# reflow_ofen.net
KiCad netlist of a schematic drawn in EAGLE
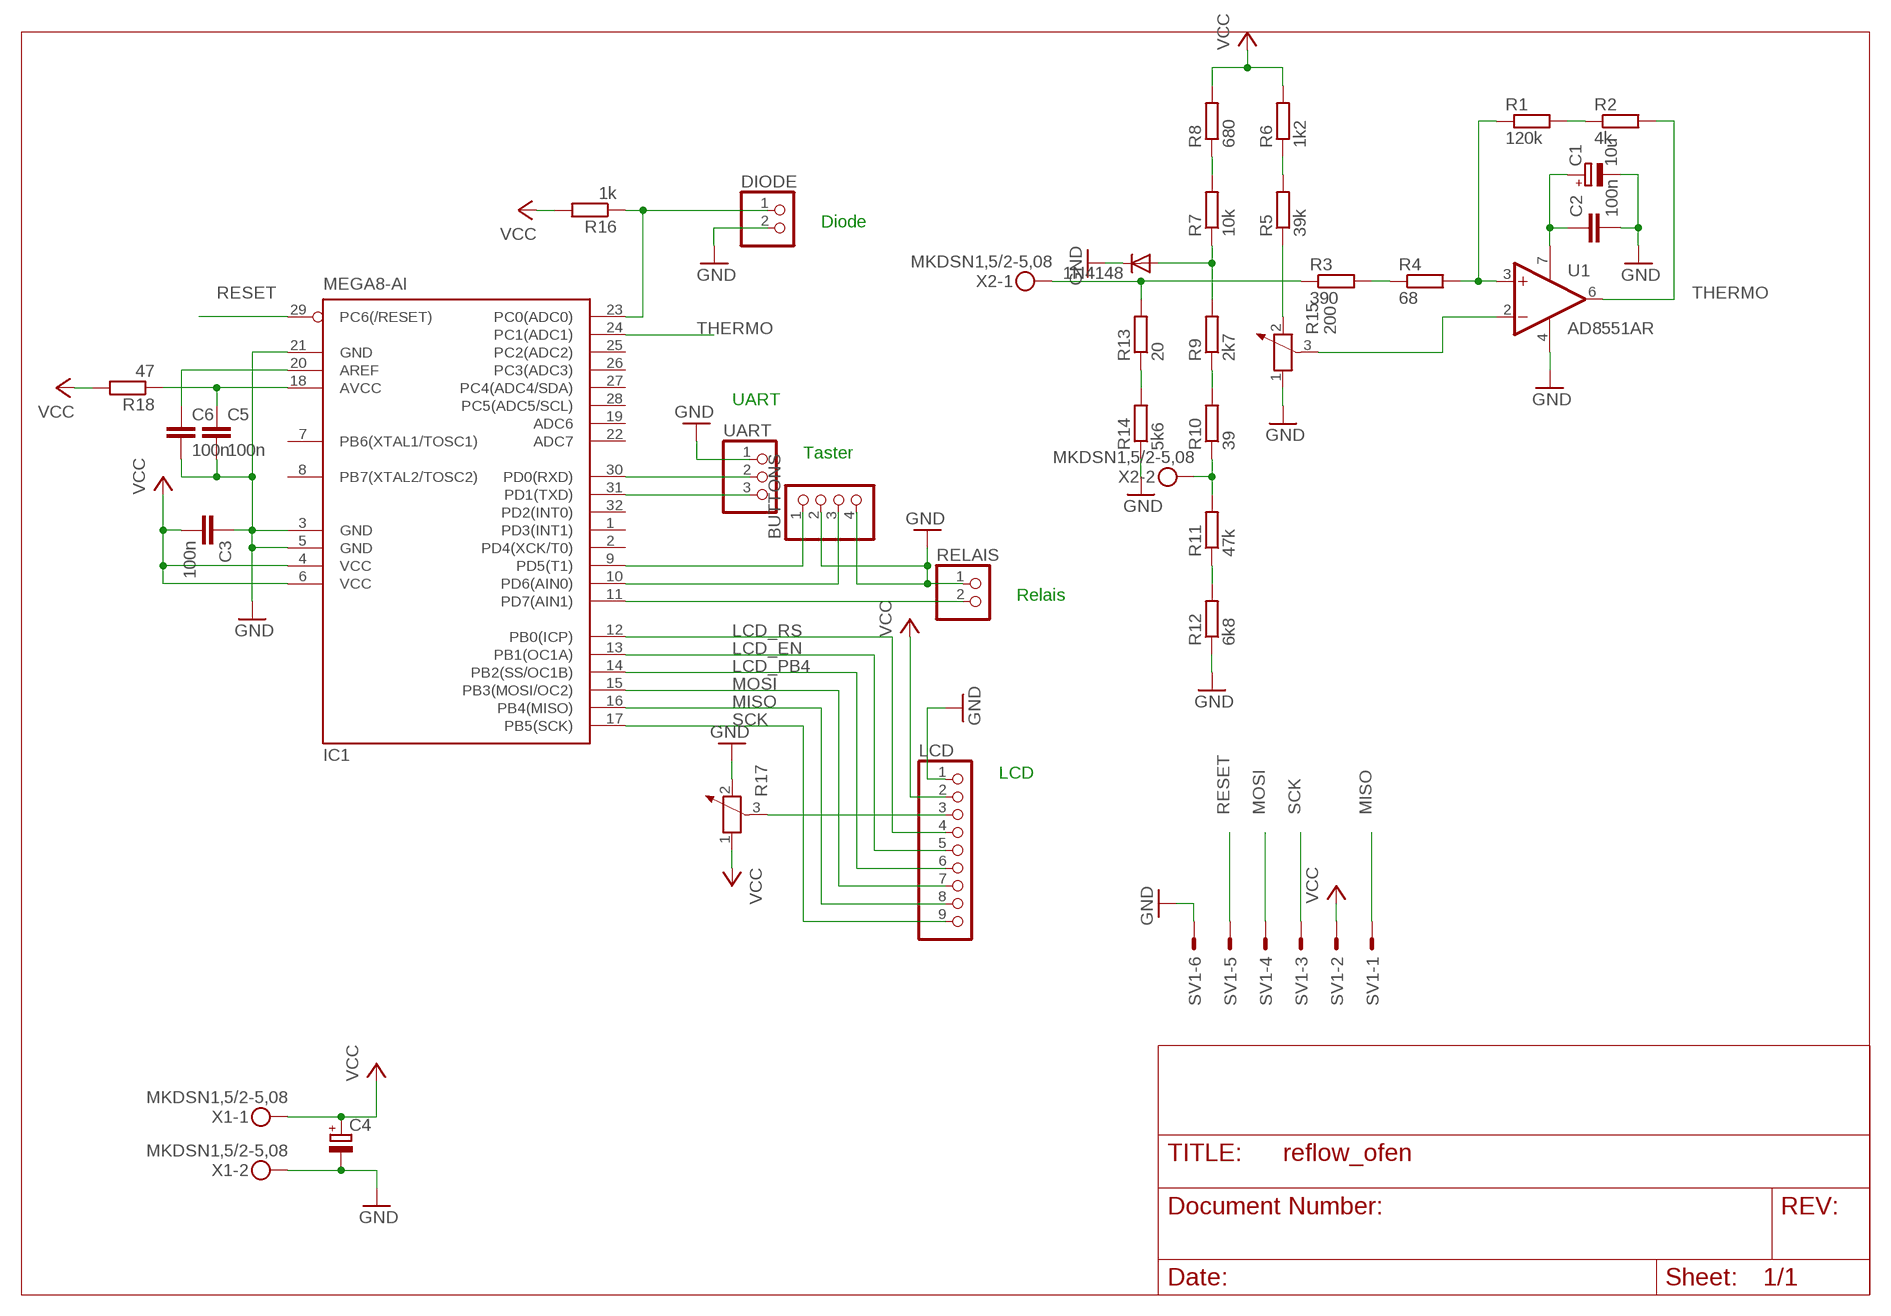
[diagram p0: schematic, sheet 1]

(export (version "E")
  (design (tool "Eeschema 10.0.6"))
  (components
    (comp (ref "1N4148")
      (value "DIODE-SOD80C")
      (footprint "eagle-import:SOD80C")
      (libsource (lib "eagle-import") (part "DIODE-SOD80C"))
    )
    (comp (ref "BUTTONS")
      (value "PINHD-1X4")
      (footprint "eagle-import:1X04")
      (libsource (lib "eagle-import") (part "PINHD-1X4"))
    )
    (comp (ref "C1")
      (value "10u")
      (footprint "eagle-import:153CLV-0405")
      (libsource (lib "eagle-import") (part "CPOL-EU153CLV-0405"))
    )
    (comp (ref "C2")
      (value "100n")
      (footprint "eagle-import:C0805")
      (libsource (lib "eagle-import") (part "C-EUC0805"))
    )
    (comp (ref "C3")
      (value "100n")
      (footprint "eagle-import:C0805")
      (libsource (lib "eagle-import") (part "C-EUC0805"))
    )
    (comp (ref "C4")
      (value "CPOL-EU153CLV-0505")
      (footprint "eagle-import:153CLV-0505")
      (libsource (lib "eagle-import") (part "CPOL-EU153CLV-0505"))
    )
    (comp (ref "C5")
      (value "100n")
      (footprint "eagle-import:C0805")
      (libsource (lib "eagle-import") (part "C-EUC0805"))
    )
    (comp (ref "C6")
      (value "100n")
      (footprint "eagle-import:C0805")
      (libsource (lib "eagle-import") (part "C-EUC0805"))
    )
    (comp (ref "DIODE")
      (value "PINHD-1X2")
      (footprint "eagle-import:1X02")
      (libsource (lib "eagle-import") (part "PINHD-1X2"))
    )
    (comp (ref "IC1")
      (value "MEGA8-AI")
      (footprint "eagle-import:TQFP32-08")
      (fields (field (name "MPN") "ATMEGA8-16AU"))
      (libsource (lib "eagle-import") (part "MEGA8-AI"))
    )
    (comp (ref "LCD")
      (value "PINHD-1X9")
      (footprint "eagle-import:1X09")
      (libsource (lib "eagle-import") (part "PINHD-1X9"))
    )
    (comp (ref "R1")
      (value "120k")
      (footprint "eagle-import:R0805")
      (libsource (lib "eagle-import") (part "R-EU_R0805"))
    )
    (comp (ref "R2")
      (value "4k")
      (footprint "eagle-import:R0805")
      (libsource (lib "eagle-import") (part "R-EU_R0805"))
    )
    (comp (ref "R3")
      (value "390")
      (footprint "eagle-import:R0805")
      (libsource (lib "eagle-import") (part "R-EU_R0805"))
    )
    (comp (ref "R4")
      (value "68")
      (footprint "eagle-import:R0805")
      (libsource (lib "eagle-import") (part "R-EU_R0805"))
    )
    (comp (ref "R5")
      (value "39k")
      (footprint "eagle-import:R0805")
      (libsource (lib "eagle-import") (part "R-EU_R0805"))
    )
    (comp (ref "R6")
      (value "1k2")
      (footprint "eagle-import:R0805")
      (libsource (lib "eagle-import") (part "R-EU_R0805"))
    )
    (comp (ref "R7")
      (value "10k")
      (footprint "eagle-import:R0805")
      (libsource (lib "eagle-import") (part "R-EU_R0805"))
    )
    (comp (ref "R8")
      (value "680")
      (footprint "eagle-import:R0805")
      (libsource (lib "eagle-import") (part "R-EU_R0805"))
    )
    (comp (ref "R9")
      (value "2k7")
      (footprint "eagle-import:R0805")
      (libsource (lib "eagle-import") (part "R-EU_R0805"))
    )
    (comp (ref "R10")
      (value "39")
      (footprint "eagle-import:R0805")
      (libsource (lib "eagle-import") (part "R-EU_R0805"))
    )
    (comp (ref "R11")
      (value "47k")
      (footprint "eagle-import:R0805")
      (libsource (lib "eagle-import") (part "R-EU_R0805"))
    )
    (comp (ref "R12")
      (value "6k8")
      (footprint "eagle-import:R0805")
      (libsource (lib "eagle-import") (part "R-EU_R0805"))
    )
    (comp (ref "R13")
      (value "20")
      (footprint "eagle-import:R0805")
      (libsource (lib "eagle-import") (part "R-EU_R0805"))
    )
    (comp (ref "R14")
      (value "5k6")
      (footprint "eagle-import:R0805")
      (libsource (lib "eagle-import") (part "R-EU_R0805"))
    )
    (comp (ref "R15")
      (value "200")
      (footprint "eagle-import:PT-10")
      (libsource (lib "eagle-import") (part "POTENTIOMETER_PT-10"))
    )
    (comp (ref "R16")
      (value "1k")
      (footprint "eagle-import:R0805")
      (libsource (lib "eagle-import") (part "R-EU_R0805"))
    )
    (comp (ref "R17")
      (value "POTENTIOMETER_PT-10")
      (footprint "eagle-import:PT-10")
      (libsource (lib "eagle-import") (part "POTENTIOMETER_PT-10"))
    )
    (comp (ref "R18")
      (value "47")
      (footprint "eagle-import:R0805")
      (libsource (lib "eagle-import") (part "R-EU_R0805"))
    )
    (comp (ref "RELAIS")
      (value "PINHD-1X2")
      (footprint "eagle-import:1X02")
      (libsource (lib "eagle-import") (part "PINHD-1X2"))
    )
    (comp (ref "SV1")
      (value "ML6E")
      (footprint "eagle-import:ML6")
      (libsource (lib "eagle-import") (part "ML6E"))
    )
    (comp (ref "U1")
      (value "AD8551AR")
      (footprint "eagle-import:SO8")
      (libsource (lib "eagle-import") (part "AD8551RA"))
    )
    (comp (ref "UART")
      (value "PINHD-1X3")
      (footprint "eagle-import:1X03")
      (libsource (lib "eagle-import") (part "PINHD-1X3"))
    )
    (comp (ref "X1")
      (value "MKDSN1,5/2-5,08")
      (footprint "eagle-import:MKDSN1,5_2-5,08")
      (fields (field (name "MPN") "MKDSN 1,5/2-5.08"))
      (libsource (lib "eagle-import") (part "MKDSN1,5/2-5,08"))
    )
    (comp (ref "X2")
      (value "MKDSN1,5/2-5,08")
      (footprint "eagle-import:MKDSN1,5_2-5,08")
      (fields (field (name "MPN") "MKDSN 1,5/2-5.08"))
      (libsource (lib "eagle-import") (part "MKDSN1,5/2-5,08"))
    )
  )
  (nets
    (net (code "1") (name "/LCD_EN") (class "Default")
      (node (ref "IC1") (pin "13") (pinfunction "PB1(OC1A)_13") (pintype "bidirectional"))
      (node (ref "LCD") (pin "5") (pinfunction "5_5") (pintype "passive"))
    )
    (net (code "2") (name "/LCD_PB4") (class "Default")
      (node (ref "IC1") (pin "14") (pinfunction "PB2(SS/OC1B)_14") (pintype "bidirectional"))
      (node (ref "LCD") (pin "6") (pinfunction "6_6") (pintype "passive"))
    )
    (net (code "3") (name "/LCD_RS") (class "Default")
      (node (ref "IC1") (pin "12") (pinfunction "PB0(ICP)_12") (pintype "bidirectional"))
      (node (ref "LCD") (pin "4") (pinfunction "4_4") (pintype "passive"))
    )
    (net (code "4") (name "/MISO") (class "Default")
      (node (ref "IC1") (pin "16") (pinfunction "PB4(MISO)_16") (pintype "bidirectional"))
      (node (ref "LCD") (pin "8") (pinfunction "8_8") (pintype "passive"))
      (node (ref "SV1") (pin "1") (pinfunction "S_1") (pintype "passive"))
    )
    (net (code "5") (name "/MOSI") (class "Default")
      (node (ref "IC1") (pin "15") (pinfunction "PB3(MOSI/OC2)_15") (pintype "bidirectional"))
      (node (ref "LCD") (pin "7") (pinfunction "7_7") (pintype "passive"))
      (node (ref "SV1") (pin "4") (pinfunction "S_4") (pintype "passive"))
    )
    (net (code "6") (name "/RESET") (class "Default")
      (node (ref "IC1") (pin "29") (pinfunction "PC6(/RESET)_29") (pintype "bidirectional"))
      (node (ref "SV1") (pin "5") (pinfunction "S_5") (pintype "passive"))
    )
    (net (code "7") (name "/SCK") (class "Default")
      (node (ref "IC1") (pin "17") (pinfunction "PB5(SCK)_17") (pintype "bidirectional"))
      (node (ref "LCD") (pin "9") (pinfunction "9_9") (pintype "passive"))
      (node (ref "SV1") (pin "3") (pinfunction "S_3") (pintype "passive"))
    )
    (net (code "8") (name "/THERMO") (class "Default")
      (node (ref "IC1") (pin "24") (pinfunction "PC1(ADC1)_24") (pintype "bidirectional"))
      (node (ref "R2") (pin "2") (pinfunction "2_2") (pintype "passive"))
      (node (ref "U1") (pin "6") (pinfunction "OUT_6") (pintype "output"))
    )
    (net (code "9") (name "GND") (class "Default")
      (node (ref "1N4148") (pin "C") (pinfunction "C_C") (pintype "passive"))
      (node (ref "BUTTONS") (pin "2") (pinfunction "2_2") (pintype "passive"))
      (node (ref "BUTTONS") (pin "4") (pinfunction "4_4") (pintype "passive"))
      (node (ref "C1") (pin "-") (pinfunction "-_-") (pintype "passive"))
      (node (ref "C2") (pin "2") (pinfunction "2_2") (pintype "passive"))
      (node (ref "C3") (pin "1") (pinfunction "1_1") (pintype "passive"))
      (node (ref "C4") (pin "-") (pinfunction "-_-") (pintype "passive"))
      (node (ref "C5") (pin "2") (pinfunction "2_2") (pintype "passive"))
      (node (ref "C6") (pin "2") (pinfunction "2_2") (pintype "passive"))
      (node (ref "DIODE") (pin "2") (pinfunction "2_2") (pintype "passive"))
      (node (ref "IC1") (pin "21") (pinfunction "GND_21") (pintype "power_in"))
      (node (ref "IC1") (pin "3") (pinfunction "GND_3") (pintype "power_in"))
      (node (ref "IC1") (pin "5") (pinfunction "GND_5") (pintype "power_in"))
      (node (ref "LCD") (pin "1") (pinfunction "1_1") (pintype "passive"))
      (node (ref "R12") (pin "1") (pinfunction "1_1") (pintype "passive"))
      (node (ref "R14") (pin "1") (pinfunction "1_1") (pintype "passive"))
      (node (ref "R15") (pin "1") (pinfunction "1_1") (pintype "passive"))
      (node (ref "R17") (pin "2") (pinfunction "2_2") (pintype "passive"))
      (node (ref "RELAIS") (pin "1") (pinfunction "1_1") (pintype "passive"))
      (node (ref "SV1") (pin "6") (pinfunction "S_6") (pintype "passive"))
      (node (ref "U1") (pin "4") (pinfunction "GND_4") (pintype "power_in"))
      (node (ref "UART") (pin "1") (pinfunction "1_1") (pintype "passive"))
      (node (ref "X1") (pin "2") (pinfunction "KL_2") (pintype "passive"))
    )
    (net (code "10") (name "Net-(1N4148-PadA)") (class "Default")
      (node (ref "1N4148") (pin "A") (pinfunction "A_A") (pintype "passive"))
      (node (ref "R7") (pin "1") (pinfunction "1_1") (pintype "passive"))
      (node (ref "R9") (pin "2") (pinfunction "2_2") (pintype "passive"))
    )
    (net (code "11") (name "Net-(IC1-AREF)") (class "Default")
      (node (ref "C6") (pin "1") (pinfunction "1_1") (pintype "passive"))
      (node (ref "IC1") (pin "20") (pinfunction "AREF_20") (pintype "passive"))
    )
    (net (code "12") (name "Net-(IC1-AVCC)") (class "Default")
      (node (ref "C5") (pin "1") (pinfunction "1_1") (pintype "passive"))
      (node (ref "IC1") (pin "18") (pinfunction "AVCC_18") (pintype "power_in"))
      (node (ref "R18") (pin "1") (pinfunction "1_1") (pintype "passive"))
    )
    (net (code "13") (name "Net-(IC1-PC0(ADC0))") (class "Default")
      (node (ref "DIODE") (pin "1") (pinfunction "1_1") (pintype "passive"))
      (node (ref "IC1") (pin "23") (pinfunction "PC0(ADC0)_23") (pintype "bidirectional"))
      (node (ref "R16") (pin "1") (pinfunction "1_1") (pintype "passive"))
    )
    (net (code "14") (name "Net-(IC1-PD0(RXD))") (class "Default")
      (node (ref "IC1") (pin "30") (pinfunction "PD0(RXD)_30") (pintype "bidirectional"))
      (node (ref "UART") (pin "2") (pinfunction "2_2") (pintype "passive"))
    )
    (net (code "15") (name "Net-(IC1-PD1(TXD))") (class "Default")
      (node (ref "IC1") (pin "31") (pinfunction "PD1(TXD)_31") (pintype "bidirectional"))
      (node (ref "UART") (pin "3") (pinfunction "3_3") (pintype "passive"))
    )
    (net (code "16") (name "Net-(IC1-PD5(T1))") (class "Default")
      (node (ref "BUTTONS") (pin "1") (pinfunction "1_1") (pintype "passive"))
      (node (ref "IC1") (pin "9") (pinfunction "PD5(T1)_9") (pintype "bidirectional"))
    )
    (net (code "17") (name "Net-(IC1-PD6(AIN0))") (class "Default")
      (node (ref "BUTTONS") (pin "3") (pinfunction "3_3") (pintype "passive"))
      (node (ref "IC1") (pin "10") (pinfunction "PD6(AIN0)_10") (pintype "bidirectional"))
    )
    (net (code "18") (name "Net-(IC1-PD7(AIN1))") (class "Default")
      (node (ref "IC1") (pin "11") (pinfunction "PD7(AIN1)_11") (pintype "bidirectional"))
      (node (ref "RELAIS") (pin "2") (pinfunction "2_2") (pintype "passive"))
    )
    (net (code "19") (name "Net-(LCD-Pad3)") (class "Default")
      (node (ref "LCD") (pin "3") (pinfunction "3_3") (pintype "passive"))
      (node (ref "R17") (pin "3") (pinfunction "3_3") (pintype "passive"))
    )
    (net (code "20") (name "Net-(R1-Pad2)") (class "Default")
      (node (ref "R1") (pin "2") (pinfunction "2_2") (pintype "passive"))
      (node (ref "R2") (pin "1") (pinfunction "1_1") (pintype "passive"))
    )
    (net (code "21") (name "Net-(R3-Pad2)") (class "Default")
      (node (ref "R3") (pin "2") (pinfunction "2_2") (pintype "passive"))
      (node (ref "R4") (pin "1") (pinfunction "1_1") (pintype "passive"))
    )
    (net (code "22") (name "Net-(R5-Pad2)") (class "Default")
      (node (ref "R5") (pin "2") (pinfunction "2_2") (pintype "passive"))
      (node (ref "R6") (pin "1") (pinfunction "1_1") (pintype "passive"))
    )
    (net (code "23") (name "Net-(R7-Pad2)") (class "Default")
      (node (ref "R7") (pin "2") (pinfunction "2_2") (pintype "passive"))
      (node (ref "R8") (pin "1") (pinfunction "1_1") (pintype "passive"))
    )
    (net (code "24") (name "Net-(R10-Pad2)") (class "Default")
      (node (ref "R10") (pin "2") (pinfunction "2_2") (pintype "passive"))
      (node (ref "R9") (pin "1") (pinfunction "1_1") (pintype "passive"))
    )
    (net (code "25") (name "Net-(R11-Pad1)") (class "Default")
      (node (ref "R11") (pin "1") (pinfunction "1_1") (pintype "passive"))
      (node (ref "R12") (pin "2") (pinfunction "2_2") (pintype "passive"))
    )
    (net (code "26") (name "Net-(R13-Pad1)") (class "Default")
      (node (ref "R13") (pin "1") (pinfunction "1_1") (pintype "passive"))
      (node (ref "R14") (pin "2") (pinfunction "2_2") (pintype "passive"))
    )
    (net (code "27") (name "Net-(R15-Pad2)") (class "Default")
      (node (ref "R15") (pin "2") (pinfunction "2_2") (pintype "passive"))
      (node (ref "R5") (pin "1") (pinfunction "1_1") (pintype "passive"))
    )
    (net (code "28") (name "Net-(U1-+IN)") (class "Default")
      (node (ref "R1") (pin "1") (pinfunction "1_1") (pintype "passive"))
      (node (ref "R4") (pin "2") (pinfunction "2_2") (pintype "passive"))
      (node (ref "U1") (pin "3") (pinfunction "+IN_3") (pintype "input"))
    )
    (net (code "29") (name "Net-(U1--IN)") (class "Default")
      (node (ref "R15") (pin "3") (pinfunction "3_3") (pintype "passive"))
      (node (ref "U1") (pin "2") (pinfunction "-IN_2") (pintype "input"))
    )
    (net (code "30") (name "Net-(U1-V+)") (class "Default")
      (node (ref "C1") (pin "+") (pinfunction "+_+") (pintype "passive"))
      (node (ref "C2") (pin "1") (pinfunction "1_1") (pintype "passive"))
      (node (ref "U1") (pin "7") (pinfunction "V+_7") (pintype "power_in"))
    )
    (net (code "31") (name "Net-(X2A-KL)") (class "Default")
      (node (ref "R13") (pin "2") (pinfunction "2_2") (pintype "passive"))
      (node (ref "R3") (pin "1") (pinfunction "1_1") (pintype "passive"))
      (node (ref "X2") (pin "1") (pinfunction "KL_1") (pintype "passive"))
    )
    (net (code "32") (name "Net-(X2B-KL)") (class "Default")
      (node (ref "R10") (pin "1") (pinfunction "1_1") (pintype "passive"))
      (node (ref "R11") (pin "2") (pinfunction "2_2") (pintype "passive"))
      (node (ref "X2") (pin "2") (pinfunction "KL_2") (pintype "passive"))
    )
    (net (code "33") (name "VCC") (class "Default")
      (node (ref "C3") (pin "2") (pinfunction "2_2") (pintype "passive"))
      (node (ref "C4") (pin "+") (pinfunction "+_+") (pintype "passive"))
      (node (ref "IC1") (pin "4") (pinfunction "VCC_4") (pintype "power_in"))
      (node (ref "IC1") (pin "6") (pinfunction "VCC_6") (pintype "power_in"))
      (node (ref "LCD") (pin "2") (pinfunction "2_2") (pintype "passive"))
      (node (ref "R16") (pin "2") (pinfunction "2_2") (pintype "passive"))
      (node (ref "R17") (pin "1") (pinfunction "1_1") (pintype "passive"))
      (node (ref "R18") (pin "2") (pinfunction "2_2") (pintype "passive"))
      (node (ref "R6") (pin "2") (pinfunction "2_2") (pintype "passive"))
      (node (ref "R8") (pin "2") (pinfunction "2_2") (pintype "passive"))
      (node (ref "SV1") (pin "2") (pinfunction "S_2") (pintype "passive"))
      (node (ref "X1") (pin "1") (pinfunction "KL_1") (pintype "passive"))
    )
    (net (code "34") (name "unconnected-(IC1-ADC6-Pad19)") (class "Default")
      (node (ref "IC1") (pin "19") (pinfunction "ADC6_19") (pintype "bidirectional"))
    )
    (net (code "35") (name "unconnected-(IC1-ADC7-Pad22)") (class "Default")
      (node (ref "IC1") (pin "22") (pinfunction "ADC7_22") (pintype "bidirectional"))
    )
    (net (code "36") (name "unconnected-(IC1-PB6(XTAL1{slash}TOSC1)-Pad7)") (class "Default")
      (node (ref "IC1") (pin "7") (pinfunction "PB6(XTAL1/TOSC1)_7") (pintype "bidirectional"))
    )
    (net (code "37") (name "unconnected-(IC1-PB7(XTAL2{slash}TOSC2)-Pad8)") (class "Default")
      (node (ref "IC1") (pin "8") (pinfunction "PB7(XTAL2/TOSC2)_8") (pintype "bidirectional"))
    )
    (net (code "38") (name "unconnected-(IC1-PC2(ADC2)-Pad25)") (class "Default")
      (node (ref "IC1") (pin "25") (pinfunction "PC2(ADC2)_25") (pintype "bidirectional"))
    )
    (net (code "39") (name "unconnected-(IC1-PC3(ADC3)-Pad26)") (class "Default")
      (node (ref "IC1") (pin "26") (pinfunction "PC3(ADC3)_26") (pintype "bidirectional"))
    )
    (net (code "40") (name "unconnected-(IC1-PC4(ADC4{slash}SDA)-Pad27)") (class "Default")
      (node (ref "IC1") (pin "27") (pinfunction "PC4(ADC4/SDA)_27") (pintype "bidirectional"))
    )
    (net (code "41") (name "unconnected-(IC1-PC5(ADC5{slash}SCL)-Pad28)") (class "Default")
      (node (ref "IC1") (pin "28") (pinfunction "PC5(ADC5/SCL)_28") (pintype "bidirectional"))
    )
    (net (code "42") (name "unconnected-(IC1-PD2(INT0)-Pad32)") (class "Default")
      (node (ref "IC1") (pin "32") (pinfunction "PD2(INT0)_32") (pintype "bidirectional"))
    )
    (net (code "43") (name "unconnected-(IC1-PD3(INT1)-Pad1)") (class "Default")
      (node (ref "IC1") (pin "1") (pinfunction "PD3(INT1)_1") (pintype "bidirectional"))
    )
    (net (code "44") (name "unconnected-(IC1-PD4(XCK{slash}T0)-Pad2)") (class "Default")
      (node (ref "IC1") (pin "2") (pinfunction "PD4(XCK/T0)_2") (pintype "bidirectional"))
    )
  )
)
